# power.net
KiCad netlist of a schematic drawn in Altium Designer
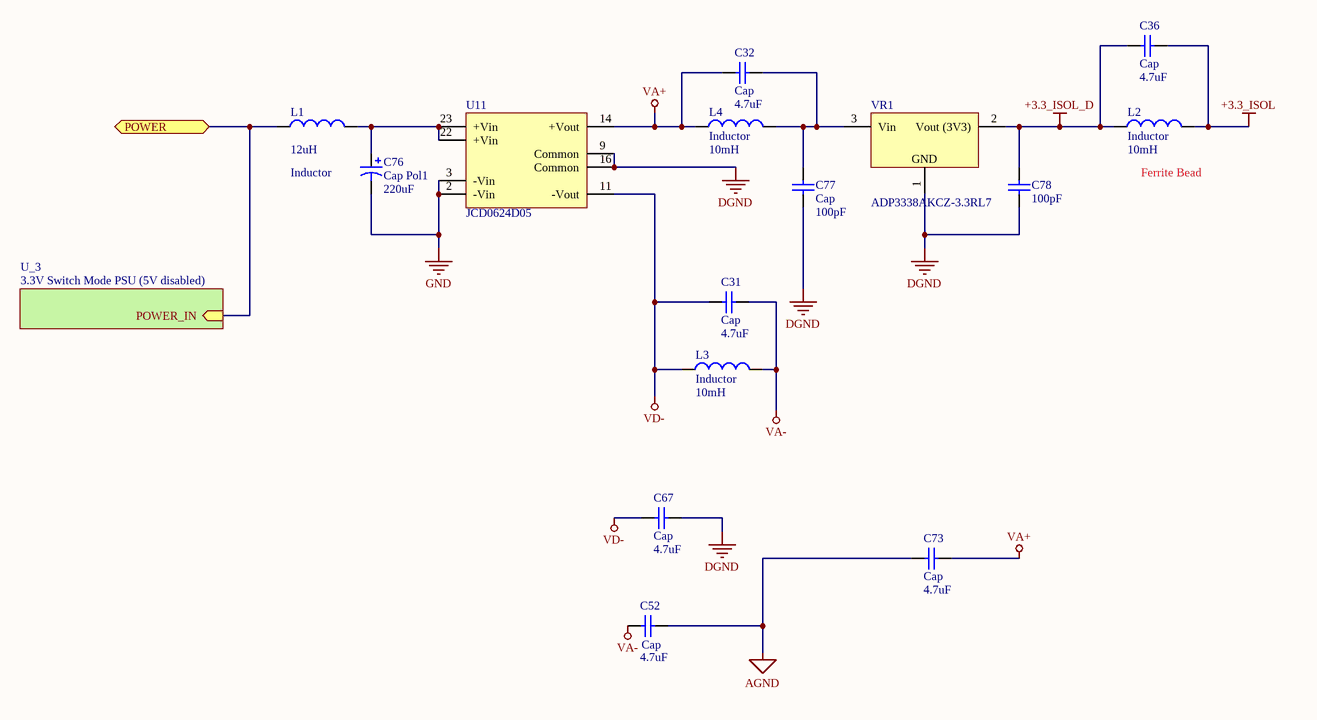
[diagram p0: power.SchDoc]

(export (version "E")
  (design (tool "Eeschema 10.0.6"))
  (components
    (comp (ref "C31")
      (value "Cap")
      (footprint "C0603")
      (description "Capacitor")
      (fields (field (name "ALTIUM_VALUE") "4.7uF") (field (name "PUBLISHER") "Altium Limited"))
      (libsource (lib "Miscellaneous Devices") (part "Cap"))
    )
    (comp (ref "C32")
      (value "Cap")
      (footprint "C0603")
      (description "Capacitor")
      (fields (field (name "ALTIUM_VALUE") "4.7uF") (field (name "PUBLISHER") "Altium Limited"))
      (libsource (lib "Miscellaneous Devices") (part "Cap"))
    )
    (comp (ref "C36")
      (value "Cap")
      (footprint "C0603")
      (description "Capacitor")
      (fields (field (name "ALTIUM_VALUE") "4.7uF") (field (name "PUBLISHER") "Altium Limited"))
      (libsource (lib "Miscellaneous Devices") (part "Cap"))
    )
    (comp (ref "C52")
      (value "Cap")
      (footprint "C0603")
      (description "Capacitor")
      (fields (field (name "ALTIUM_VALUE") "4.7uF") (field (name "PUBLISHER") "Altium Limited"))
      (libsource (lib "Miscellaneous Devices") (part "Cap"))
    )
    (comp (ref "C67")
      (value "Cap")
      (footprint "C0603")
      (description "Capacitor")
      (fields (field (name "ALTIUM_VALUE") "4.7uF") (field (name "PUBLISHER") "Altium Limited"))
      (libsource (lib "Miscellaneous Devices") (part "Cap"))
    )
    (comp (ref "C73")
      (value "Cap")
      (footprint "C0603")
      (description "Capacitor")
      (fields (field (name "ALTIUM_VALUE") "4.7uF") (field (name "PUBLISHER") "Altium Limited"))
      (libsource (lib "Miscellaneous Devices") (part "Cap"))
    )
    (comp (ref "C76")
      (value "Cap Pol1")
      (footprint "Capacitor")
      (description "Polarized Capacitor (Radial)")
      (fields (field (name "ALTIUM_VALUE") "220uF") (field (name "PUBLISHER") "Altium Limited"))
      (libsource (lib "Miscellaneous Devices") (part "Cap Pol1"))
    )
    (comp (ref "C77")
      (value "Cap")
      (footprint "C0805")
      (description "Capacitor")
      (fields (field (name "ALTIUM_VALUE") "100pF") (field (name "PUBLISHER") "Altium Limited"))
      (libsource (lib "Miscellaneous Devices") (part "Cap"))
    )
    (comp (ref "C78")
      (value "100pF")
      (footprint "C0805")
      (description "Capacitor")
      (fields (field (name "Comment") "Cap") (field (name "PUBLISHER") "Altium Limited"))
      (libsource (lib "Miscellaneous Devices") (part "Cap"))
    )
    (comp (ref "L1")
      (value "Inductor")
      (footprint "SDR0604-150YL")
      (fields (field (name "ALTIUM_VALUE") "12uH") (field (name "PUBLISHER") "Altium Limited"))
      (libsource (lib "Miscellaneous Devices") (part "Inductor"))
    )
    (comp (ref "L2")
      (value "Inductor")
      (footprint "C0805")
      (fields (field (name "ALTIUM_VALUE") "10mH") (field (name "PUBLISHER") "Altium Limited"))
      (libsource (lib "Miscellaneous Devices") (part "Inductor"))
    )
    (comp (ref "L3")
      (value "Inductor")
      (footprint "C0805")
      (fields (field (name "ALTIUM_VALUE") "10mH") (field (name "PUBLISHER") "Altium Limited"))
      (libsource (lib "Miscellaneous Devices") (part "Inductor"))
    )
    (comp (ref "L4")
      (value "Inductor")
      (footprint "C0805")
      (fields (field (name "ALTIUM_VALUE") "10mH") (field (name "PUBLISHER") "Altium Limited"))
      (libsource (lib "Miscellaneous Devices") (part "Inductor"))
    )
    (comp (ref "U11")
      (value "JCD0624D05")
      (footprint "DIP24")
      (description "DC/DC CONVERTER, 6W, +/-5V, DIP-24")
      (libsource (lib "JCD0624S12") (part "JCD0624D05"))
    )
    (comp (ref "VR1")
      (value "ADP3338AKCZ-3.3RL7")
      (footprint "ADP3338AKCZ-3.3RL7")
      (description "3.3V LDO Regulator")
      (libsource (lib "ADP3338AKCZ-3.3RL7 (3V3 LDO)") (part "ADP3338AKCZ-3.3RL7"))
    )
  )
  (nets
    (net (code "1") (name "+3.3_ISOL") (class "Default")
      (node (ref "C36") (pin "2") (pinfunction "2_2") (pintype "passive"))
      (node (ref "L2") (pin "2") (pinfunction "2_2") (pintype "passive"))
    )
    (net (code "2") (name "+3.3_ISOL_D") (class "Default")
      (node (ref "C36") (pin "1") (pinfunction "1_1") (pintype "passive"))
      (node (ref "C78") (pin "1") (pinfunction "1_1") (pintype "passive"))
      (node (ref "L2") (pin "1") (pinfunction "1_1") (pintype "passive"))
      (node (ref "VR1") (pin "2") (pinfunction "Vout_(3V3)_2") (pintype "power_in"))
    )
    (net (code "3") (name "/POWER") (class "Default")
      (node (ref "L1") (pin "1") (pinfunction "1_1") (pintype "passive"))
    )
    (net (code "4") (name "AGND") (class "Default")
      (node (ref "C52") (pin "2") (pinfunction "2_2") (pintype "passive"))
      (node (ref "C73") (pin "1") (pinfunction "1_1") (pintype "passive"))
    )
    (net (code "5") (name "DGND") (class "Default")
      (node (ref "C67") (pin "2") (pinfunction "2_2") (pintype "passive"))
      (node (ref "C77") (pin "1") (pinfunction "1_1") (pintype "passive"))
      (node (ref "C78") (pin "2") (pinfunction "2_2") (pintype "passive"))
      (node (ref "U11") (pin "16") (pinfunction "Common_16") (pintype "power_in"))
      (node (ref "U11") (pin "9") (pinfunction "Common_9") (pintype "power_in"))
      (node (ref "VR1") (pin "1") (pinfunction "GND_1") (pintype "power_in"))
    )
    (net (code "6") (name "GND") (class "Default")
      (node (ref "C76") (pin "2") (pinfunction "2_2") (pintype "passive"))
      (node (ref "U11") (pin "2") (pinfunction "-Vin_2") (pintype "power_in"))
      (node (ref "U11") (pin "3") (pinfunction "-Vin_3") (pintype "power_in"))
    )
    (net (code "7") (name "Net-(C76-Pad1)") (class "Default")
      (node (ref "C76") (pin "1") (pinfunction "1_1") (pintype "passive"))
      (node (ref "L1") (pin "2") (pinfunction "2_2") (pintype "passive"))
      (node (ref "U11") (pin "22") (pinfunction "+Vin_22") (pintype "power_in"))
      (node (ref "U11") (pin "23") (pinfunction "+Vin_23") (pintype "power_in"))
    )
    (net (code "8") (name "Net-(VR1-Vin)") (class "Default")
      (node (ref "C32") (pin "2") (pinfunction "2_2") (pintype "passive"))
      (node (ref "C77") (pin "2") (pinfunction "2_2") (pintype "passive"))
      (node (ref "L4") (pin "2") (pinfunction "2_2") (pintype "passive"))
      (node (ref "VR1") (pin "3") (pinfunction "Vin_3") (pintype "power_in"))
    )
    (net (code "9") (name "VA+") (class "Default")
      (node (ref "C32") (pin "1") (pinfunction "1_1") (pintype "passive"))
      (node (ref "C73") (pin "2") (pinfunction "2_2") (pintype "passive"))
      (node (ref "L4") (pin "1") (pinfunction "1_1") (pintype "passive"))
      (node (ref "U11") (pin "14") (pinfunction "+Vout_14") (pintype "power_in"))
    )
    (net (code "10") (name "VA-") (class "Default")
      (node (ref "C31") (pin "2") (pinfunction "2_2") (pintype "passive"))
      (node (ref "C52") (pin "1") (pinfunction "1_1") (pintype "passive"))
      (node (ref "L3") (pin "2") (pinfunction "2_2") (pintype "passive"))
    )
    (net (code "11") (name "VD-") (class "Default")
      (node (ref "C31") (pin "1") (pinfunction "1_1") (pintype "passive"))
      (node (ref "C67") (pin "1") (pinfunction "1_1") (pintype "passive"))
      (node (ref "L3") (pin "1") (pinfunction "1_1") (pintype "passive"))
      (node (ref "U11") (pin "11") (pinfunction "-Vout_11") (pintype "power_in"))
    )
  )
)
